# Rpi_LED_Indicator.net
KiCad netlist of a schematic drawn in Altium Designer
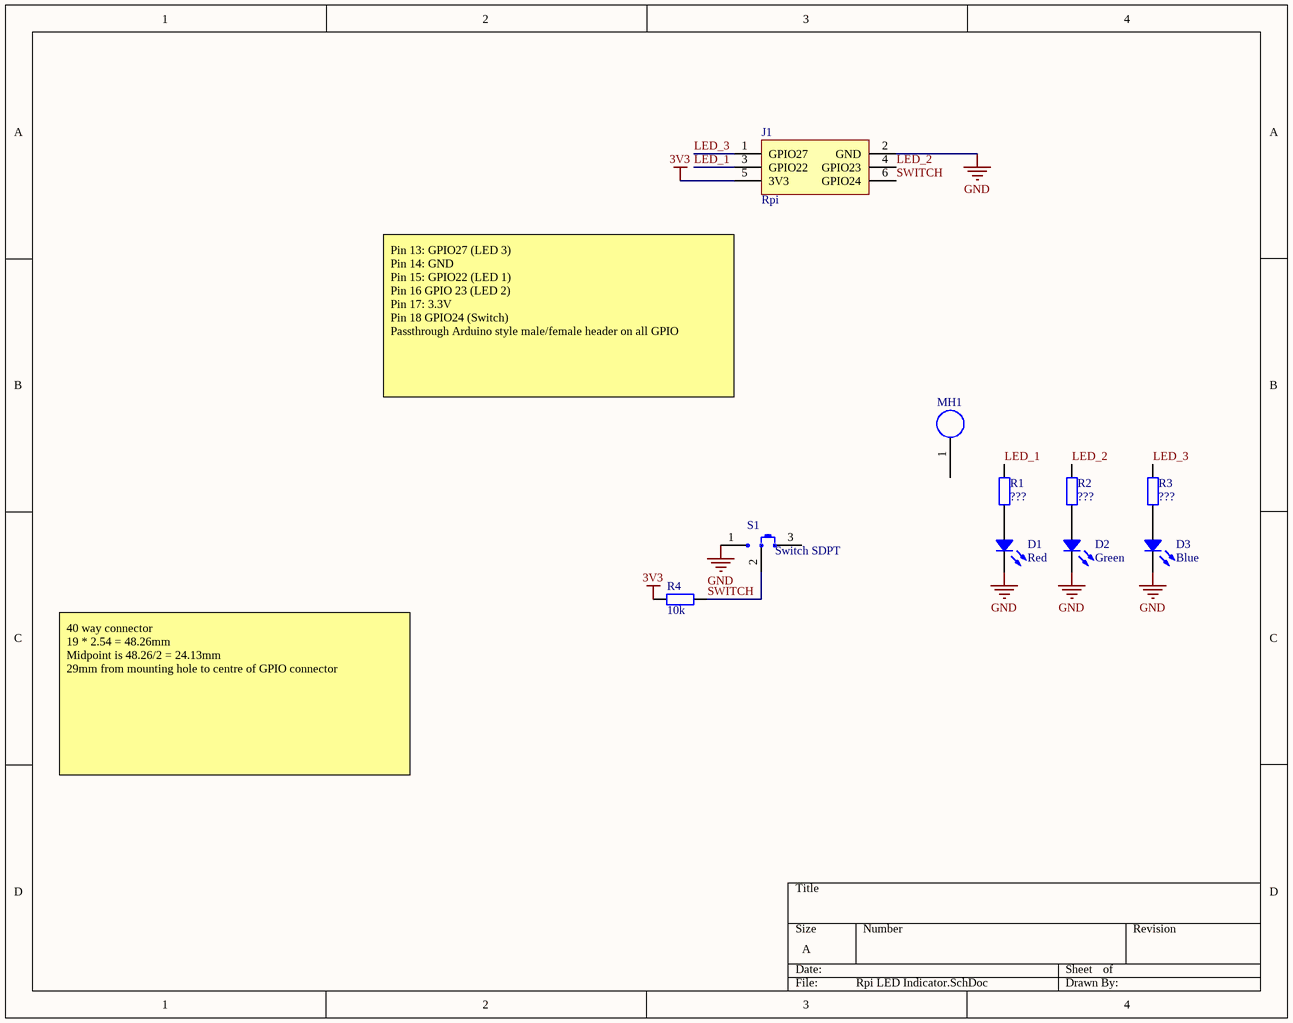
[diagram p0: Rpi LED Indicator.SchDoc]

(export (version "E")
  (design (tool "Eeschema 10.0.6"))
  (components
    (comp (ref "D1")
      (value "Red")
      (footprint "LED 0603_1608 RED")
      (description "LED RED 0603 SMD")
      (fields (field (name "PART NUMBER") "5973005507F") (field (name "MANUFACTURER") "Dialight"))
      (libsource (lib "Celestial Altium Library") (part "LED"))
    )
    (comp (ref "D2")
      (value "Green")
      (footprint "LED 0603_1608 GREEN")
      (description "LED GREEN DIFFUSED CHIP SMD")
      (fields (field (name "PART NUMBER") "HSMG-C197") (field (name "MANUFACTURER") "Broadcom Limited"))
      (libsource (lib "Celestial Altium Library - altium_library") (part "LED"))
    )
    (comp (ref "D3")
      (value "Blue")
      (footprint "LED 0603_1608 BLUE")
      (description "LED BLUE 0603 SMD")
      (fields (field (name "PART NUMBER") "5973604507F") (field (name "MANUFACTURER") "Dialight"))
      (libsource (lib "Celestial Altium Library") (part "LED"))
    )
    (comp (ref "J1")
      (value "Rpi")
      (footprint "2.54mm header female 6POS")
      (libsource (lib "Power Library") (part "Rpi 2x3 header"))
    )
    (comp (ref "MH1")
      (value "AUX_1")
      (footprint "M2.5 Mounting Hole")
      (libsource (lib "Ethernet Serial Library") (part "Mounting Hole"))
    )
    (comp (ref "R1")
      (value "???")
      (footprint "0603_R")
      (fields (field (name "Comment") "Res 0603"))
      (libsource (lib "Power Library") (part "Res 0603"))
    )
    (comp (ref "R2")
      (value "???")
      (footprint "0603_R")
      (fields (field (name "Comment") "Res 0603"))
      (libsource (lib "Power Library") (part "Res 0603"))
    )
    (comp (ref "R3")
      (value "???")
      (footprint "0603_R")
      (fields (field (name "Comment") "Res 0603"))
      (libsource (lib "Power Library") (part "Res 0603"))
    )
    (comp (ref "R4")
      (value "10k")
      (footprint "0603_R")
      (fields (field (name "Comment") "Res 0603"))
      (libsource (lib "") (part "Res 0603_1"))
    )
    (comp (ref "S1")
      (value "Switch SDPT")
      (footprint "Switch Nidec Copal CL-SB-12A-11T")
      (description "SWITCH SLIDE SPDT")
      (libsource (lib "Power Library") (part "Switch SDPT"))
    )
  )
  (nets
    (net (code "1") (name "/LED_1") (class "Default")
      (node (ref "J1") (pin "3") (pinfunction "GPIO22_3") (pintype "passive"))
      (node (ref "R1") (pin "1") (pinfunction "1_1") (pintype "passive"))
    )
    (net (code "2") (name "/LED_2") (class "Default")
      (node (ref "J1") (pin "4") (pinfunction "GPIO23_4") (pintype "passive"))
      (node (ref "R2") (pin "1") (pinfunction "1_1") (pintype "passive"))
    )
    (net (code "3") (name "/LED_3") (class "Default")
      (node (ref "J1") (pin "1") (pinfunction "GPIO27_1") (pintype "passive"))
      (node (ref "R3") (pin "1") (pinfunction "1_1") (pintype "passive"))
    )
    (net (code "4") (name "/SWITCH") (class "Default")
      (node (ref "J1") (pin "6") (pinfunction "GPIO24_6") (pintype "passive"))
      (node (ref "R4") (pin "2") (pinfunction "2_2") (pintype "passive"))
      (node (ref "S1") (pin "2") (pinfunction "COM_2") (pintype "passive"))
    )
    (net (code "5") (name "3V3") (class "Default")
      (node (ref "J1") (pin "5") (pinfunction "3V3_5") (pintype "passive"))
      (node (ref "R4") (pin "1") (pinfunction "1_1") (pintype "passive"))
    )
    (net (code "6") (name "GND") (class "Default")
      (node (ref "D1") (pin "2") (pinfunction "2_2") (pintype "passive"))
      (node (ref "D2") (pin "2") (pinfunction "2_2") (pintype "passive"))
      (node (ref "D3") (pin "2") (pinfunction "2_2") (pintype "passive"))
      (node (ref "J1") (pin "2") (pinfunction "GND_2") (pintype "passive"))
      (node (ref "S1") (pin "1") (pinfunction "1_1") (pintype "passive"))
    )
    (net (code "7") (name "Net-(D1-Pad1)") (class "Default")
      (node (ref "D1") (pin "1") (pinfunction "1_1") (pintype "passive"))
      (node (ref "R1") (pin "2") (pinfunction "2_2") (pintype "passive"))
    )
    (net (code "8") (name "Net-(D2-Pad1)") (class "Default")
      (node (ref "D2") (pin "1") (pinfunction "1_1") (pintype "passive"))
      (node (ref "R2") (pin "2") (pinfunction "2_2") (pintype "passive"))
    )
    (net (code "9") (name "Net-(D3-Pad1)") (class "Default")
      (node (ref "D3") (pin "1") (pinfunction "1_1") (pintype "passive"))
      (node (ref "R3") (pin "2") (pinfunction "2_2") (pintype "passive"))
    )
    (net (code "10") (name "unconnected-(MH1-Pad1)") (class "Default")
      (node (ref "MH1") (pin "1") (pintype "passive"))
    )
    (net (code "11") (name "unconnected-(S1-Pad3)") (class "Default")
      (node (ref "S1") (pin "3") (pinfunction "3_3") (pintype "passive"))
    )
  )
)
